# STM32_power_expander.net
KiCad netlist of a schematic drawn in EAGLE
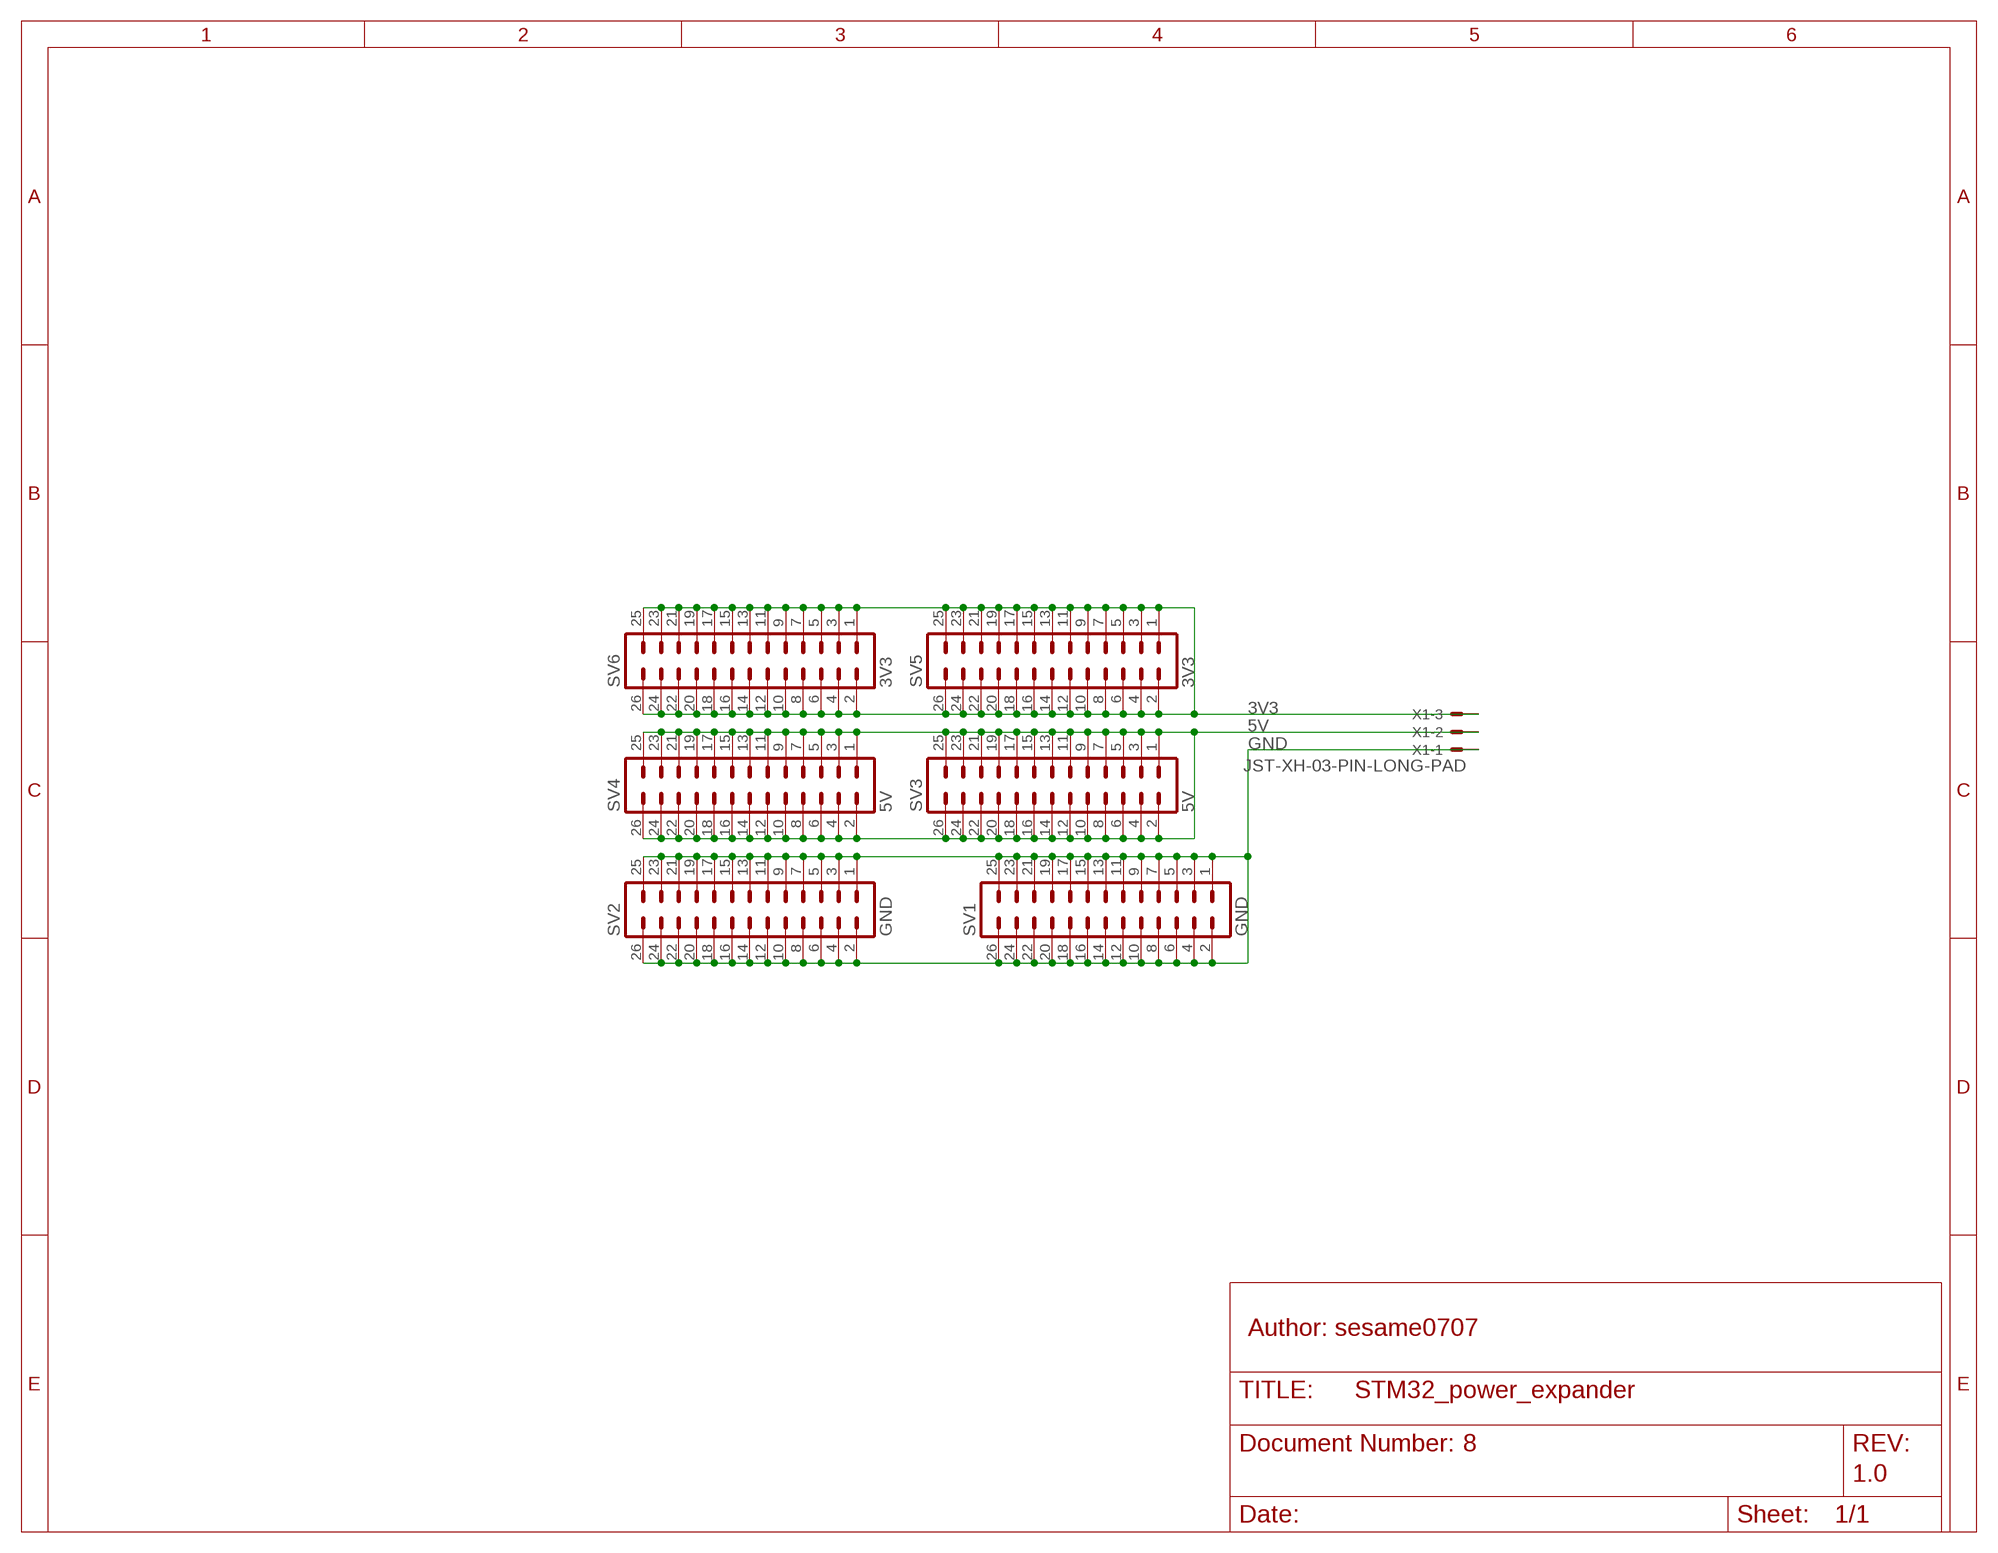
[diagram p0: schematic, sheet 1]

(export (version "E")
  (design (tool "Eeschema 10.0.6"))
  (components
    (comp (ref "SV1")
      (value "GND")
      (footprint "eagle-import:MA13-2")
      (libsource (lib "eagle-import") (part "MA13-2"))
    )
    (comp (ref "SV2")
      (value "GND")
      (footprint "eagle-import:MA13-2")
      (libsource (lib "eagle-import") (part "MA13-2"))
    )
    (comp (ref "SV3")
      (value "5V")
      (footprint "eagle-import:MA13-2")
      (libsource (lib "eagle-import") (part "MA13-2"))
    )
    (comp (ref "SV4")
      (value "5V")
      (footprint "eagle-import:MA13-2")
      (libsource (lib "eagle-import") (part "MA13-2"))
    )
    (comp (ref "SV5")
      (value "3V3")
      (footprint "eagle-import:MA13-2")
      (libsource (lib "eagle-import") (part "MA13-2"))
    )
    (comp (ref "SV6")
      (value "3V3")
      (footprint "eagle-import:MA13-2")
      (libsource (lib "eagle-import") (part "MA13-2"))
    )
    (comp (ref "X1")
      (value "JST-XH-03-PIN-LONG-PAD")
      (footprint "eagle-import:JST-XH-03-PACKAGE-LONG-PAD")
      (libsource (lib "eagle-import") (part "JST-XH-03-PIN-LONG-PAD"))
    )
  )
  (nets
    (net (code "1") (name "/3V3") (class "Default")
      (node (ref "SV5") (pin "1") (pinfunction "1_1") (pintype "passive"))
      (node (ref "SV5") (pin "10") (pinfunction "10_10") (pintype "passive"))
      (node (ref "SV5") (pin "11") (pinfunction "11_11") (pintype "passive"))
      (node (ref "SV5") (pin "12") (pinfunction "12_12") (pintype "passive"))
      (node (ref "SV5") (pin "13") (pinfunction "13_13") (pintype "passive"))
      (node (ref "SV5") (pin "14") (pinfunction "14_14") (pintype "passive"))
      (node (ref "SV5") (pin "15") (pinfunction "15_15") (pintype "passive"))
      (node (ref "SV5") (pin "16") (pinfunction "16_16") (pintype "passive"))
      (node (ref "SV5") (pin "17") (pinfunction "17_17") (pintype "passive"))
      (node (ref "SV5") (pin "18") (pinfunction "18_18") (pintype "passive"))
      (node (ref "SV5") (pin "19") (pinfunction "19_19") (pintype "passive"))
      (node (ref "SV5") (pin "2") (pinfunction "2_2") (pintype "passive"))
      (node (ref "SV5") (pin "20") (pinfunction "20_20") (pintype "passive"))
      (node (ref "SV5") (pin "21") (pinfunction "21_21") (pintype "passive"))
      (node (ref "SV5") (pin "22") (pinfunction "22_22") (pintype "passive"))
      (node (ref "SV5") (pin "23") (pinfunction "23_23") (pintype "passive"))
      (node (ref "SV5") (pin "24") (pinfunction "24_24") (pintype "passive"))
      (node (ref "SV5") (pin "25") (pinfunction "25_25") (pintype "passive"))
      (node (ref "SV5") (pin "26") (pinfunction "26_26") (pintype "passive"))
      (node (ref "SV5") (pin "3") (pinfunction "3_3") (pintype "passive"))
      (node (ref "SV5") (pin "4") (pinfunction "4_4") (pintype "passive"))
      (node (ref "SV5") (pin "5") (pinfunction "5_5") (pintype "passive"))
      (node (ref "SV5") (pin "6") (pinfunction "6_6") (pintype "passive"))
      (node (ref "SV5") (pin "7") (pinfunction "7_7") (pintype "passive"))
      (node (ref "SV5") (pin "8") (pinfunction "8_8") (pintype "passive"))
      (node (ref "SV5") (pin "9") (pinfunction "9_9") (pintype "passive"))
      (node (ref "SV6") (pin "1") (pinfunction "1_1") (pintype "passive"))
      (node (ref "SV6") (pin "10") (pinfunction "10_10") (pintype "passive"))
      (node (ref "SV6") (pin "11") (pinfunction "11_11") (pintype "passive"))
      (node (ref "SV6") (pin "12") (pinfunction "12_12") (pintype "passive"))
      (node (ref "SV6") (pin "13") (pinfunction "13_13") (pintype "passive"))
      (node (ref "SV6") (pin "14") (pinfunction "14_14") (pintype "passive"))
      (node (ref "SV6") (pin "15") (pinfunction "15_15") (pintype "passive"))
      (node (ref "SV6") (pin "16") (pinfunction "16_16") (pintype "passive"))
      (node (ref "SV6") (pin "17") (pinfunction "17_17") (pintype "passive"))
      (node (ref "SV6") (pin "18") (pinfunction "18_18") (pintype "passive"))
      (node (ref "SV6") (pin "19") (pinfunction "19_19") (pintype "passive"))
      (node (ref "SV6") (pin "2") (pinfunction "2_2") (pintype "passive"))
      (node (ref "SV6") (pin "20") (pinfunction "20_20") (pintype "passive"))
      (node (ref "SV6") (pin "21") (pinfunction "21_21") (pintype "passive"))
      (node (ref "SV6") (pin "22") (pinfunction "22_22") (pintype "passive"))
      (node (ref "SV6") (pin "23") (pinfunction "23_23") (pintype "passive"))
      (node (ref "SV6") (pin "24") (pinfunction "24_24") (pintype "passive"))
      (node (ref "SV6") (pin "25") (pinfunction "25_25") (pintype "passive"))
      (node (ref "SV6") (pin "26") (pinfunction "26_26") (pintype "passive"))
      (node (ref "SV6") (pin "3") (pinfunction "3_3") (pintype "passive"))
      (node (ref "SV6") (pin "4") (pinfunction "4_4") (pintype "passive"))
      (node (ref "SV6") (pin "5") (pinfunction "5_5") (pintype "passive"))
      (node (ref "SV6") (pin "6") (pinfunction "6_6") (pintype "passive"))
      (node (ref "SV6") (pin "7") (pinfunction "7_7") (pintype "passive"))
      (node (ref "SV6") (pin "8") (pinfunction "8_8") (pintype "passive"))
      (node (ref "SV6") (pin "9") (pinfunction "9_9") (pintype "passive"))
      (node (ref "X1") (pin "3") (pinfunction "S_3") (pintype "passive"))
    )
    (net (code "2") (name "/5V") (class "Default")
      (node (ref "SV3") (pin "1") (pinfunction "1_1") (pintype "passive"))
      (node (ref "SV3") (pin "10") (pinfunction "10_10") (pintype "passive"))
      (node (ref "SV3") (pin "11") (pinfunction "11_11") (pintype "passive"))
      (node (ref "SV3") (pin "12") (pinfunction "12_12") (pintype "passive"))
      (node (ref "SV3") (pin "13") (pinfunction "13_13") (pintype "passive"))
      (node (ref "SV3") (pin "14") (pinfunction "14_14") (pintype "passive"))
      (node (ref "SV3") (pin "15") (pinfunction "15_15") (pintype "passive"))
      (node (ref "SV3") (pin "16") (pinfunction "16_16") (pintype "passive"))
      (node (ref "SV3") (pin "17") (pinfunction "17_17") (pintype "passive"))
      (node (ref "SV3") (pin "18") (pinfunction "18_18") (pintype "passive"))
      (node (ref "SV3") (pin "19") (pinfunction "19_19") (pintype "passive"))
      (node (ref "SV3") (pin "2") (pinfunction "2_2") (pintype "passive"))
      (node (ref "SV3") (pin "20") (pinfunction "20_20") (pintype "passive"))
      (node (ref "SV3") (pin "21") (pinfunction "21_21") (pintype "passive"))
      (node (ref "SV3") (pin "22") (pinfunction "22_22") (pintype "passive"))
      (node (ref "SV3") (pin "23") (pinfunction "23_23") (pintype "passive"))
      (node (ref "SV3") (pin "24") (pinfunction "24_24") (pintype "passive"))
      (node (ref "SV3") (pin "25") (pinfunction "25_25") (pintype "passive"))
      (node (ref "SV3") (pin "26") (pinfunction "26_26") (pintype "passive"))
      (node (ref "SV3") (pin "3") (pinfunction "3_3") (pintype "passive"))
      (node (ref "SV3") (pin "4") (pinfunction "4_4") (pintype "passive"))
      (node (ref "SV3") (pin "5") (pinfunction "5_5") (pintype "passive"))
      (node (ref "SV3") (pin "6") (pinfunction "6_6") (pintype "passive"))
      (node (ref "SV3") (pin "7") (pinfunction "7_7") (pintype "passive"))
      (node (ref "SV3") (pin "8") (pinfunction "8_8") (pintype "passive"))
      (node (ref "SV3") (pin "9") (pinfunction "9_9") (pintype "passive"))
      (node (ref "SV4") (pin "1") (pinfunction "1_1") (pintype "passive"))
      (node (ref "SV4") (pin "10") (pinfunction "10_10") (pintype "passive"))
      (node (ref "SV4") (pin "11") (pinfunction "11_11") (pintype "passive"))
      (node (ref "SV4") (pin "12") (pinfunction "12_12") (pintype "passive"))
      (node (ref "SV4") (pin "13") (pinfunction "13_13") (pintype "passive"))
      (node (ref "SV4") (pin "14") (pinfunction "14_14") (pintype "passive"))
      (node (ref "SV4") (pin "15") (pinfunction "15_15") (pintype "passive"))
      (node (ref "SV4") (pin "16") (pinfunction "16_16") (pintype "passive"))
      (node (ref "SV4") (pin "17") (pinfunction "17_17") (pintype "passive"))
      (node (ref "SV4") (pin "18") (pinfunction "18_18") (pintype "passive"))
      (node (ref "SV4") (pin "19") (pinfunction "19_19") (pintype "passive"))
      (node (ref "SV4") (pin "2") (pinfunction "2_2") (pintype "passive"))
      (node (ref "SV4") (pin "20") (pinfunction "20_20") (pintype "passive"))
      (node (ref "SV4") (pin "21") (pinfunction "21_21") (pintype "passive"))
      (node (ref "SV4") (pin "22") (pinfunction "22_22") (pintype "passive"))
      (node (ref "SV4") (pin "23") (pinfunction "23_23") (pintype "passive"))
      (node (ref "SV4") (pin "24") (pinfunction "24_24") (pintype "passive"))
      (node (ref "SV4") (pin "25") (pinfunction "25_25") (pintype "passive"))
      (node (ref "SV4") (pin "26") (pinfunction "26_26") (pintype "passive"))
      (node (ref "SV4") (pin "3") (pinfunction "3_3") (pintype "passive"))
      (node (ref "SV4") (pin "4") (pinfunction "4_4") (pintype "passive"))
      (node (ref "SV4") (pin "5") (pinfunction "5_5") (pintype "passive"))
      (node (ref "SV4") (pin "6") (pinfunction "6_6") (pintype "passive"))
      (node (ref "SV4") (pin "7") (pinfunction "7_7") (pintype "passive"))
      (node (ref "SV4") (pin "8") (pinfunction "8_8") (pintype "passive"))
      (node (ref "SV4") (pin "9") (pinfunction "9_9") (pintype "passive"))
      (node (ref "X1") (pin "2") (pinfunction "S_2") (pintype "passive"))
    )
    (net (code "3") (name "/GND") (class "Default")
      (node (ref "SV1") (pin "1") (pinfunction "1_1") (pintype "passive"))
      (node (ref "SV1") (pin "10") (pinfunction "10_10") (pintype "passive"))
      (node (ref "SV1") (pin "11") (pinfunction "11_11") (pintype "passive"))
      (node (ref "SV1") (pin "12") (pinfunction "12_12") (pintype "passive"))
      (node (ref "SV1") (pin "13") (pinfunction "13_13") (pintype "passive"))
      (node (ref "SV1") (pin "14") (pinfunction "14_14") (pintype "passive"))
      (node (ref "SV1") (pin "15") (pinfunction "15_15") (pintype "passive"))
      (node (ref "SV1") (pin "16") (pinfunction "16_16") (pintype "passive"))
      (node (ref "SV1") (pin "17") (pinfunction "17_17") (pintype "passive"))
      (node (ref "SV1") (pin "18") (pinfunction "18_18") (pintype "passive"))
      (node (ref "SV1") (pin "19") (pinfunction "19_19") (pintype "passive"))
      (node (ref "SV1") (pin "2") (pinfunction "2_2") (pintype "passive"))
      (node (ref "SV1") (pin "20") (pinfunction "20_20") (pintype "passive"))
      (node (ref "SV1") (pin "21") (pinfunction "21_21") (pintype "passive"))
      (node (ref "SV1") (pin "22") (pinfunction "22_22") (pintype "passive"))
      (node (ref "SV1") (pin "23") (pinfunction "23_23") (pintype "passive"))
      (node (ref "SV1") (pin "24") (pinfunction "24_24") (pintype "passive"))
      (node (ref "SV1") (pin "25") (pinfunction "25_25") (pintype "passive"))
      (node (ref "SV1") (pin "26") (pinfunction "26_26") (pintype "passive"))
      (node (ref "SV1") (pin "3") (pinfunction "3_3") (pintype "passive"))
      (node (ref "SV1") (pin "4") (pinfunction "4_4") (pintype "passive"))
      (node (ref "SV1") (pin "5") (pinfunction "5_5") (pintype "passive"))
      (node (ref "SV1") (pin "6") (pinfunction "6_6") (pintype "passive"))
      (node (ref "SV1") (pin "7") (pinfunction "7_7") (pintype "passive"))
      (node (ref "SV1") (pin "8") (pinfunction "8_8") (pintype "passive"))
      (node (ref "SV1") (pin "9") (pinfunction "9_9") (pintype "passive"))
      (node (ref "SV2") (pin "1") (pinfunction "1_1") (pintype "passive"))
      (node (ref "SV2") (pin "10") (pinfunction "10_10") (pintype "passive"))
      (node (ref "SV2") (pin "11") (pinfunction "11_11") (pintype "passive"))
      (node (ref "SV2") (pin "12") (pinfunction "12_12") (pintype "passive"))
      (node (ref "SV2") (pin "13") (pinfunction "13_13") (pintype "passive"))
      (node (ref "SV2") (pin "14") (pinfunction "14_14") (pintype "passive"))
      (node (ref "SV2") (pin "15") (pinfunction "15_15") (pintype "passive"))
      (node (ref "SV2") (pin "16") (pinfunction "16_16") (pintype "passive"))
      (node (ref "SV2") (pin "17") (pinfunction "17_17") (pintype "passive"))
      (node (ref "SV2") (pin "18") (pinfunction "18_18") (pintype "passive"))
      (node (ref "SV2") (pin "19") (pinfunction "19_19") (pintype "passive"))
      (node (ref "SV2") (pin "2") (pinfunction "2_2") (pintype "passive"))
      (node (ref "SV2") (pin "20") (pinfunction "20_20") (pintype "passive"))
      (node (ref "SV2") (pin "21") (pinfunction "21_21") (pintype "passive"))
      (node (ref "SV2") (pin "22") (pinfunction "22_22") (pintype "passive"))
      (node (ref "SV2") (pin "23") (pinfunction "23_23") (pintype "passive"))
      (node (ref "SV2") (pin "24") (pinfunction "24_24") (pintype "passive"))
      (node (ref "SV2") (pin "25") (pinfunction "25_25") (pintype "passive"))
      (node (ref "SV2") (pin "26") (pinfunction "26_26") (pintype "passive"))
      (node (ref "SV2") (pin "3") (pinfunction "3_3") (pintype "passive"))
      (node (ref "SV2") (pin "4") (pinfunction "4_4") (pintype "passive"))
      (node (ref "SV2") (pin "5") (pinfunction "5_5") (pintype "passive"))
      (node (ref "SV2") (pin "6") (pinfunction "6_6") (pintype "passive"))
      (node (ref "SV2") (pin "7") (pinfunction "7_7") (pintype "passive"))
      (node (ref "SV2") (pin "8") (pinfunction "8_8") (pintype "passive"))
      (node (ref "SV2") (pin "9") (pinfunction "9_9") (pintype "passive"))
      (node (ref "X1") (pin "1") (pinfunction "S_1") (pintype "passive"))
    )
  )
)
